# Main.net
KiCad netlist of a schematic drawn in Altium Designer
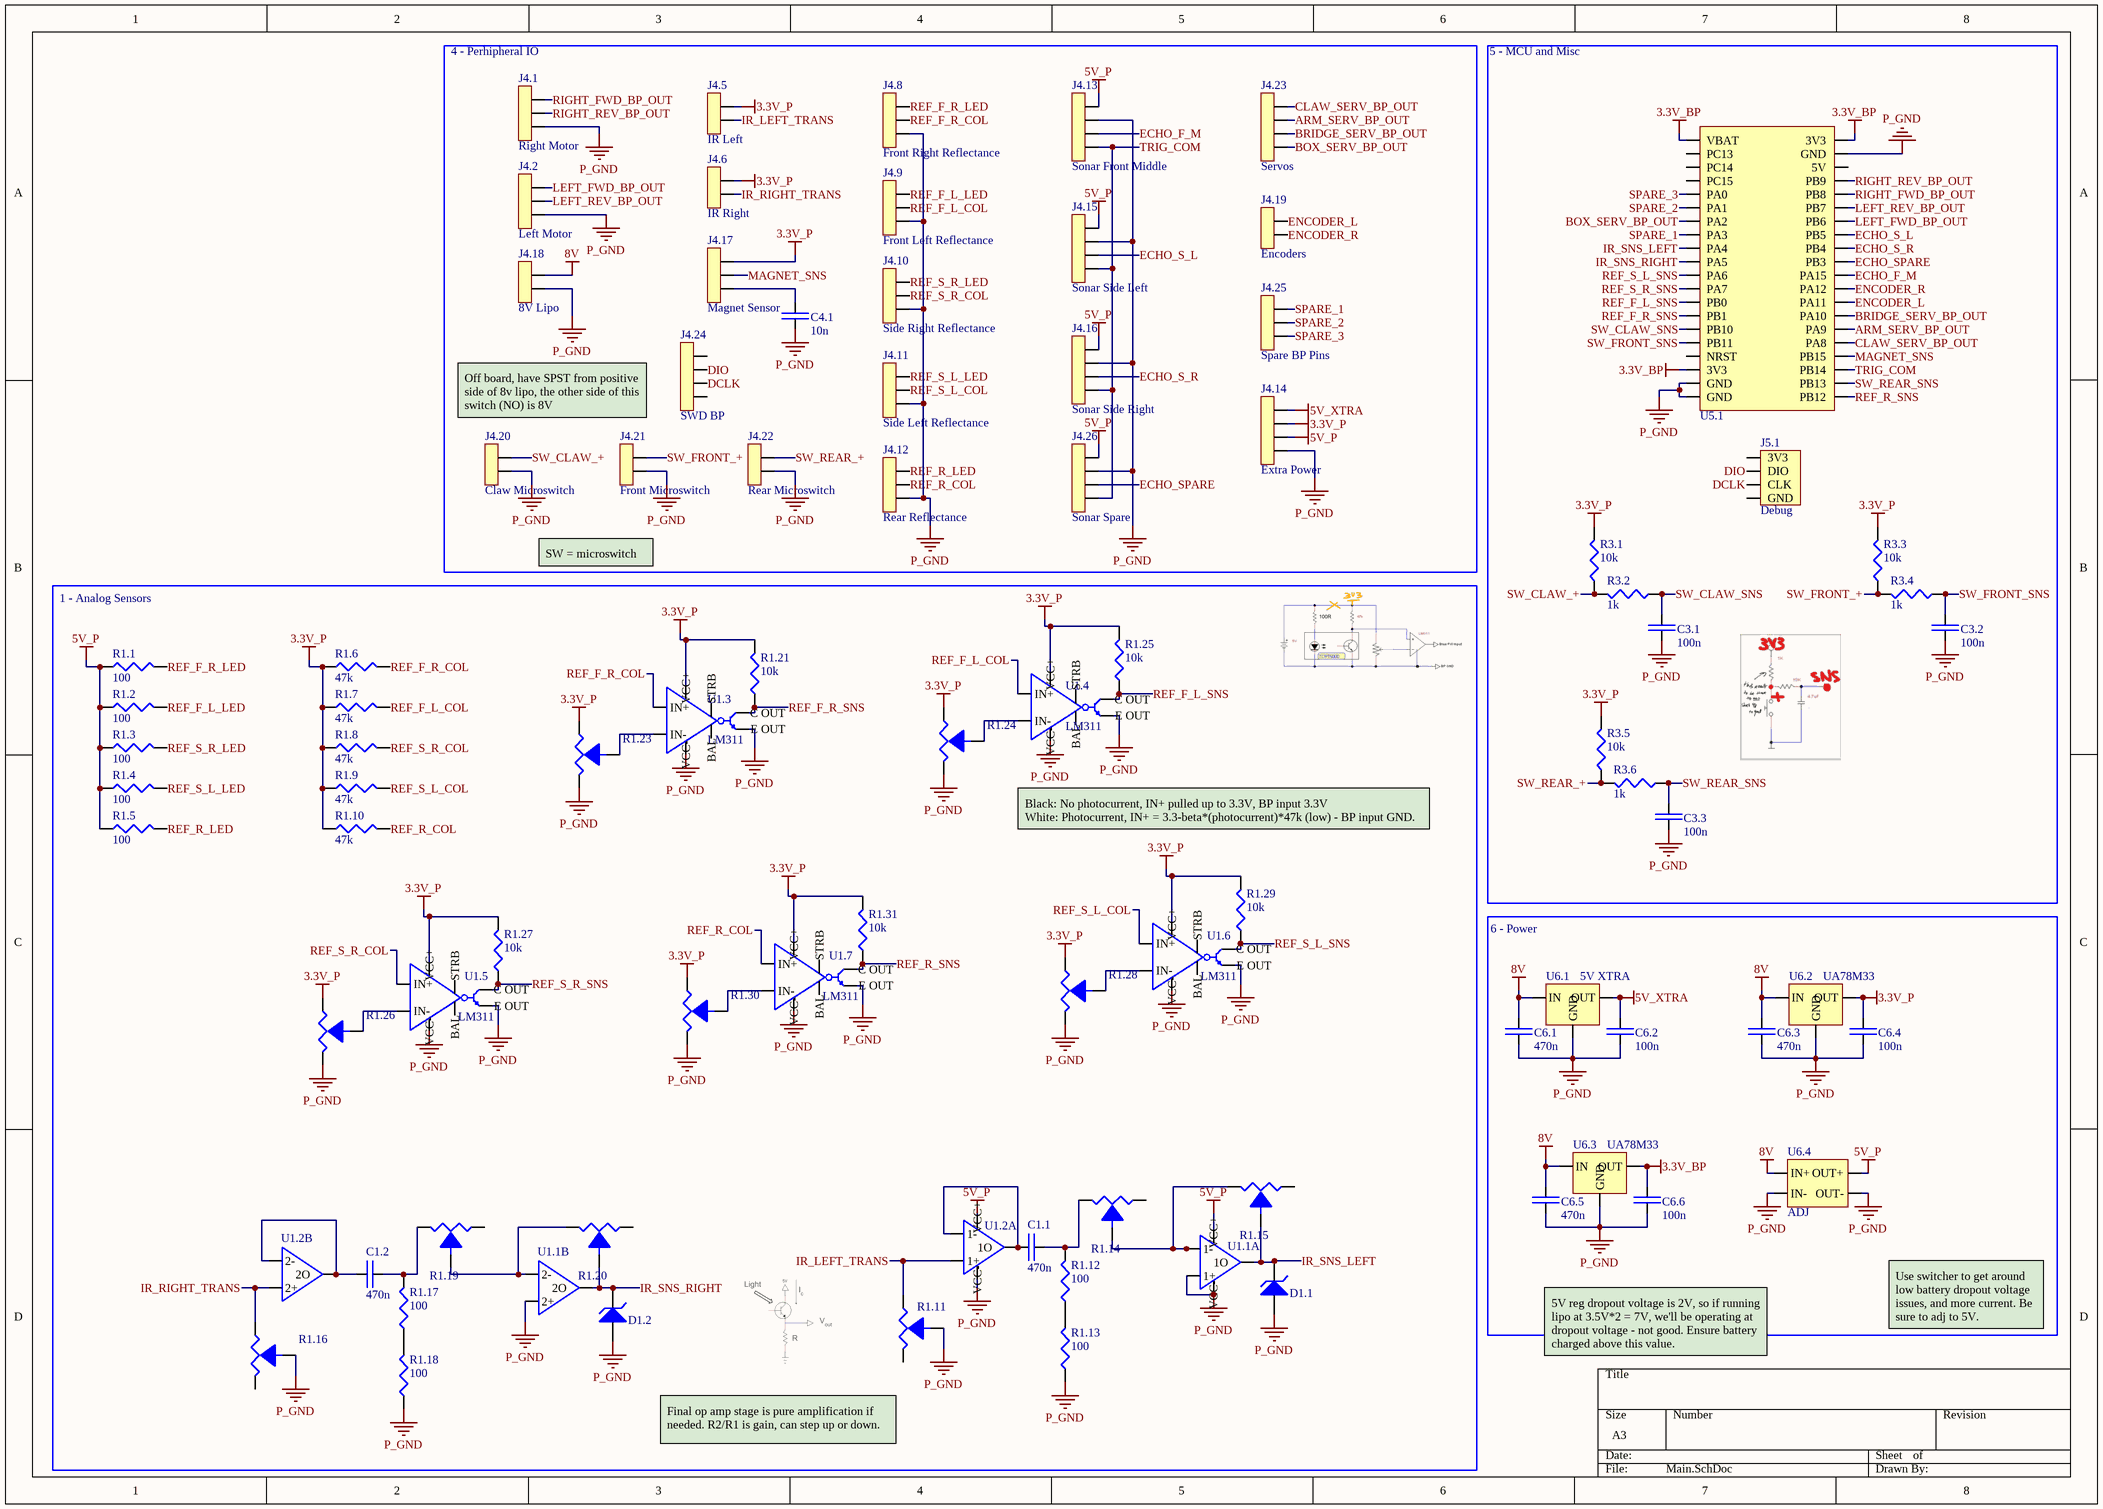
[diagram p0: Main.SchDoc]

(export (version "E")
  (design (tool "Eeschema 10.0.6"))
  (components
    (comp (ref "C1.1")
      (value "470n")
      (footprint "Non Polarized Cap")
      (libsource (lib "SPICEBot_SchLib") (part "Cap_Generic"))
    )
    (comp (ref "C1.2")
      (value "470n")
      (footprint "Non Polarized Cap")
      (libsource (lib "SPICEBot_SchLib") (part "Cap_Generic"))
    )
    (comp (ref "C3.1")
      (value "100n")
      (footprint "Non Polarized Cap")
      (libsource (lib "SPICEBot_SchLib") (part "Cap_Generic"))
    )
    (comp (ref "C3.2")
      (value "100n")
      (footprint "Non Polarized Cap")
      (libsource (lib "SPICEBot_SchLib") (part "Cap_Generic"))
    )
    (comp (ref "C3.3")
      (value "100n")
      (footprint "Non Polarized Cap")
      (libsource (lib "SPICEBot_SchLib") (part "Cap_Generic"))
    )
    (comp (ref "C4.1")
      (value "10n")
      (footprint "Non Polarized Cap")
      (libsource (lib "SPICEBot_SchLib") (part "Cap_Generic"))
    )
    (comp (ref "C6.1")
      (value "470n")
      (footprint "Non Polarized Cap")
      (libsource (lib "SPICEBot_SchLib") (part "Cap_Generic"))
    )
    (comp (ref "C6.2")
      (value "100n")
      (footprint "Non Polarized Cap")
      (libsource (lib "SPICEBot_SchLib") (part "Cap_Generic"))
    )
    (comp (ref "C6.3")
      (value "470n")
      (footprint "Non Polarized Cap")
      (libsource (lib "SPICEBot_SchLib") (part "Cap_Generic"))
    )
    (comp (ref "C6.4")
      (value "100n")
      (footprint "Non Polarized Cap")
      (libsource (lib "SPICEBot_SchLib") (part "Cap_Generic"))
    )
    (comp (ref "C6.5")
      (value "470n")
      (footprint "Non Polarized Cap")
      (libsource (lib "SPICEBot_SchLib") (part "Cap_Generic"))
    )
    (comp (ref "C6.6")
      (value "100n")
      (footprint "Non Polarized Cap")
      (libsource (lib "SPICEBot_SchLib") (part "Cap_Generic"))
    )
    (comp (ref "D1.1")
      (value "3.3V")
      (footprint "Zener Generic")
      (libsource (lib "SPICEBot_SchLib") (part "Zener_Generic"))
    )
    (comp (ref "D1.2")
      (value "3.3V")
      (footprint "Zener Generic")
      (libsource (lib "SPICEBot_SchLib") (part "Zener_Generic"))
    )
    (comp (ref "J4.1")
      (value "Right Motor")
      (footprint "3pos JST")
      (description "3pos Conn")
      (libsource (lib "SPICEBot_SchLib") (part "3pos Conn"))
    )
    (comp (ref "J4.2")
      (value "Left Motor")
      (footprint "3pos JST")
      (description "3pos Conn")
      (libsource (lib "SPICEBot_SchLib") (part "3pos Conn"))
    )
    (comp (ref "J4.5")
      (value "IR Left")
      (footprint "2pos JST")
      (description "2pos Conn JST")
      (libsource (lib "SPICEBot_SchLib") (part "2pos Conn"))
    )
    (comp (ref "J4.6")
      (value "IR Right")
      (footprint "2pos JST")
      (description "2pos Conn JST")
      (libsource (lib "SPICEBot_SchLib") (part "2pos Conn"))
    )
    (comp (ref "J4.8")
      (value "Front Right Reflectance")
      (footprint "3pos JST")
      (description "3pos Conn")
      (libsource (lib "SPICEBot_SchLib") (part "3pos Conn"))
    )
    (comp (ref "J4.9")
      (value "Front Left Reflectance")
      (footprint "3pos JST")
      (description "3pos Conn")
      (libsource (lib "SPICEBot_SchLib") (part "3pos Conn"))
    )
    (comp (ref "J4.10")
      (value "Side Right Reflectance")
      (footprint "3pos JST")
      (description "3pos Conn")
      (libsource (lib "SPICEBot_SchLib") (part "3pos Conn"))
    )
    (comp (ref "J4.11")
      (value "Side Left Reflectance")
      (footprint "3pos JST")
      (description "3pos Conn")
      (libsource (lib "SPICEBot_SchLib") (part "3pos Conn"))
    )
    (comp (ref "J4.12")
      (value "Rear Reflectance")
      (footprint "3pos JST")
      (description "3pos Conn")
      (libsource (lib "SPICEBot_SchLib") (part "3pos Conn"))
    )
    (comp (ref "J4.13")
      (value "Sonar Front Middle")
      (footprint "4Pos JST")
      (description "4pos Conn")
      (libsource (lib "SPICEBot_SchLib") (part "4pos Conn"))
    )
    (comp (ref "J4.14")
      (value "Extra Power")
      (footprint "4Pos JST")
      (description "4pos Conn")
      (libsource (lib "SPICEBot_SchLib") (part "4pos Conn"))
    )
    (comp (ref "J4.15")
      (value "Sonar Side Left")
      (footprint "4Pos JST")
      (description "4pos Conn")
      (libsource (lib "SPICEBot_SchLib") (part "4pos Conn"))
    )
    (comp (ref "J4.16")
      (value "Sonar Side Right")
      (footprint "4Pos JST")
      (description "4pos Conn")
      (libsource (lib "SPICEBot_SchLib") (part "4pos Conn"))
    )
    (comp (ref "J4.17")
      (value "Magnet Sensor")
      (footprint "3pos JST")
      (description "3pos Conn")
      (libsource (lib "SPICEBot_SchLib") (part "3pos Conn"))
    )
    (comp (ref "J4.18")
      (value "8V Lipo")
      (footprint "2pos JST")
      (description "2pos Conn JST")
      (libsource (lib "SPICEBot_SchLib") (part "2pos Conn"))
    )
    (comp (ref "J4.19")
      (value "Encoders")
      (footprint "2pos JST")
      (description "2pos Conn JST")
      (libsource (lib "SPICEBot_SchLib") (part "2pos Conn"))
    )
    (comp (ref "J4.20")
      (value "Claw Microswitch")
      (footprint "2pos JST")
      (description "2pos Conn JST")
      (libsource (lib "SPICEBot_SchLib") (part "2pos Conn"))
    )
    (comp (ref "J4.21")
      (value "Front Microswitch")
      (footprint "2pos JST")
      (description "2pos Conn JST")
      (libsource (lib "SPICEBot_SchLib") (part "2pos Conn"))
    )
    (comp (ref "J4.22")
      (value "Rear Microswitch")
      (footprint "2pos JST")
      (description "2pos Conn JST")
      (libsource (lib "SPICEBot_SchLib") (part "2pos Conn"))
    )
    (comp (ref "J4.23")
      (value "Servos")
      (footprint "4Pos JST")
      (description "4pos Conn")
      (libsource (lib "SPICEBot_SchLib") (part "4pos Conn"))
    )
    (comp (ref "J4.24")
      (value "SWD BP")
      (footprint "4Pos JST")
      (description "4pos Conn")
      (libsource (lib "SPICEBot_SchLib") (part "4pos Conn"))
    )
    (comp (ref "J4.25")
      (value "Spare BP Pins")
      (footprint "3pos JST")
      (description "3pos Conn")
      (libsource (lib "SPICEBot_SchLib") (part "3pos Conn"))
    )
    (comp (ref "J4.26")
      (value "Sonar Spare")
      (footprint "4Pos JST")
      (description "4pos Conn")
      (libsource (lib "SPICEBot_SchLib") (part "4pos Conn"))
    )
    (comp (ref "J5.1")
      (value "Debug")
      (footprint "Four Pads")
      (libsource (lib "SPICEBot_SchLib") (part "BP SWD Conn"))
    )
    (comp (ref "R1.1")
      (value "100")
      (footprint "Res_Generic")
      (libsource (lib "SPICEBot_SchLib") (part "Res_Generic"))
    )
    (comp (ref "R1.2")
      (value "100")
      (footprint "Res_Generic")
      (libsource (lib "SPICEBot_SchLib") (part "Res_Generic"))
    )
    (comp (ref "R1.3")
      (value "100")
      (footprint "Res_Generic")
      (libsource (lib "SPICEBot_SchLib") (part "Res_Generic"))
    )
    (comp (ref "R1.4")
      (value "100")
      (footprint "Res_Generic")
      (libsource (lib "SPICEBot_SchLib") (part "Res_Generic"))
    )
    (comp (ref "R1.5")
      (value "100")
      (footprint "Res_Generic")
      (libsource (lib "SPICEBot_SchLib") (part "Res_Generic"))
    )
    (comp (ref "R1.6")
      (value "47k")
      (footprint "Res_Generic")
      (libsource (lib "SPICEBot_SchLib") (part "Res_Generic"))
    )
    (comp (ref "R1.7")
      (value "47k")
      (footprint "Res_Generic")
      (libsource (lib "SPICEBot_SchLib") (part "Res_Generic"))
    )
    (comp (ref "R1.8")
      (value "47k")
      (footprint "Res_Generic")
      (libsource (lib "SPICEBot_SchLib") (part "Res_Generic"))
    )
    (comp (ref "R1.9")
      (value "47k")
      (footprint "Res_Generic")
      (libsource (lib "SPICEBot_SchLib") (part "Res_Generic"))
    )
    (comp (ref "R1.10")
      (value "47k")
      (footprint "Res_Generic")
      (libsource (lib "SPICEBot_SchLib") (part "Res_Generic"))
    )
    (comp (ref "R1.11")
      (value "100k")
      (footprint "Pot Generic")
      (libsource (lib "SPICEBot_SchLib") (part "Pot_Generic"))
    )
    (comp (ref "R1.12")
      (value "100")
      (footprint "Res_Generic")
      (libsource (lib "SPICEBot_SchLib") (part "Res_Generic"))
    )
    (comp (ref "R1.13")
      (value "100")
      (footprint "Res_Generic")
      (libsource (lib "SPICEBot_SchLib") (part "Res_Generic"))
    )
    (comp (ref "R1.14")
      (value "10k")
      (footprint "Pot Generic")
      (libsource (lib "SPICEBot_SchLib") (part "Pot_Generic"))
    )
    (comp (ref "R1.15")
      (value "100k")
      (footprint "Pot Generic")
      (libsource (lib "SPICEBot_SchLib") (part "Pot_Generic"))
    )
    (comp (ref "R1.16")
      (value "100k")
      (footprint "Pot Generic")
      (libsource (lib "SPICEBot_SchLib") (part "Pot_Generic"))
    )
    (comp (ref "R1.17")
      (value "100")
      (footprint "Res_Generic")
      (libsource (lib "SPICEBot_SchLib") (part "Res_Generic"))
    )
    (comp (ref "R1.18")
      (value "100")
      (footprint "Res_Generic")
      (libsource (lib "SPICEBot_SchLib") (part "Res_Generic"))
    )
    (comp (ref "R1.19")
      (value "10k")
      (footprint "Pot Generic")
      (libsource (lib "SPICEBot_SchLib") (part "Pot_Generic"))
    )
    (comp (ref "R1.20")
      (value "100k")
      (footprint "Pot Generic")
      (libsource (lib "SPICEBot_SchLib") (part "Pot_Generic"))
    )
    (comp (ref "R1.21")
      (value "10k")
      (footprint "Res_Generic")
      (libsource (lib "SPICEBot_SchLib") (part "Res_Generic"))
    )
    (comp (ref "R1.23")
      (value "10k")
      (footprint "Pot Generic")
      (libsource (lib "SPICEBot_SchLib") (part "Pot_Generic"))
    )
    (comp (ref "R1.24")
      (value "10k")
      (footprint "Pot Generic")
      (libsource (lib "SPICEBot_SchLib") (part "Pot_Generic"))
    )
    (comp (ref "R1.25")
      (value "10k")
      (footprint "Res_Generic")
      (libsource (lib "SPICEBot_SchLib") (part "Res_Generic"))
    )
    (comp (ref "R1.26")
      (value "10k")
      (footprint "Pot Generic")
      (libsource (lib "SPICEBot_SchLib") (part "Pot_Generic"))
    )
    (comp (ref "R1.27")
      (value "10k")
      (footprint "Res_Generic")
      (libsource (lib "SPICEBot_SchLib") (part "Res_Generic"))
    )
    (comp (ref "R1.28")
      (value "10k")
      (footprint "Pot Generic")
      (libsource (lib "SPICEBot_SchLib") (part "Pot_Generic"))
    )
    (comp (ref "R1.29")
      (value "10k")
      (footprint "Res_Generic")
      (libsource (lib "SPICEBot_SchLib") (part "Res_Generic"))
    )
    (comp (ref "R1.30")
      (value "10k")
      (footprint "Pot Generic")
      (libsource (lib "SPICEBot_SchLib") (part "Pot_Generic"))
    )
    (comp (ref "R1.31")
      (value "10k")
      (footprint "Res_Generic")
      (libsource (lib "SPICEBot_SchLib") (part "Res_Generic"))
    )
    (comp (ref "R3.1")
      (value "10k")
      (footprint "Res_Generic")
      (libsource (lib "SPICEBot_SchLib") (part "Res_Generic"))
    )
    (comp (ref "R3.2")
      (value "1k")
      (footprint "Res_Generic")
      (libsource (lib "SPICEBot_SchLib") (part "Res_Generic"))
    )
    (comp (ref "R3.3")
      (value "10k")
      (footprint "Res_Generic")
      (libsource (lib "SPICEBot_SchLib") (part "Res_Generic"))
    )
    (comp (ref "R3.4")
      (value "1k")
      (footprint "Res_Generic")
      (libsource (lib "SPICEBot_SchLib") (part "Res_Generic"))
    )
    (comp (ref "R3.5")
      (value "10k")
      (footprint "Res_Generic")
      (libsource (lib "SPICEBot_SchLib") (part "Res_Generic"))
    )
    (comp (ref "R3.6")
      (value "1k")
      (footprint "Res_Generic")
      (libsource (lib "SPICEBot_SchLib") (part "Res_Generic"))
    )
    (comp (ref "U1.1")
      (value "TL082IP")
      (footprint "DIP8")
      (description "TL082IP IC OPAMP JFET 2 CIRCUIT 8DIP")
      (libsource (lib "SPICEBot_SchLib") (part "TL082IP Op Amp"))
    )
    (comp (ref "U1.2")
      (value "TL082IP")
      (footprint "DIP8")
      (description "TL082IP IC OPAMP JFET 2 CIRCUIT 8DIP")
      (libsource (lib "SPICEBot_SchLib") (part "TL082IP Op Amp"))
    )
    (comp (ref "U1.3")
      (value "LM311")
      (footprint "DIP8")
      (description "LM311 IC DIFF COMPARATOR STROBE 8-DIP")
      (libsource (lib "SPICEBot_SchLib") (part "LM311 Comparator"))
    )
    (comp (ref "U1.4")
      (value "LM311")
      (footprint "DIP8")
      (description "LM311 IC DIFF COMPARATOR STROBE 8-DIP")
      (libsource (lib "SPICEBot_SchLib") (part "LM311 Comparator"))
    )
    (comp (ref "U1.5")
      (value "LM311")
      (footprint "DIP8")
      (description "LM311 IC DIFF COMPARATOR STROBE 8-DIP")
      (libsource (lib "SPICEBot_SchLib") (part "LM311 Comparator"))
    )
    (comp (ref "U1.6")
      (value "LM311")
      (footprint "DIP8")
      (description "LM311 IC DIFF COMPARATOR STROBE 8-DIP")
      (libsource (lib "SPICEBot_SchLib") (part "LM311 Comparator"))
    )
    (comp (ref "U1.7")
      (value "LM311")
      (footprint "DIP8")
      (description "LM311 IC DIFF COMPARATOR STROBE 8-DIP")
      (libsource (lib "SPICEBot_SchLib") (part "LM311 Comparator"))
    )
    (comp (ref "U5.1")
      (value "Bluepill")
      (footprint "DIP40")
      (description "STM32F103C8T6")
      (libsource (lib "SPICEBot_SchLib") (part "Bluepill"))
    )
    (comp (ref "U6.1")
      (value "5V XTRA")
      (footprint "TO220")
      (description "UA7805 IC REG LINEAR 5V 1.5A TO220-3")
      (libsource (lib "SPICEBot_SchLib") (part "UA7805 5V Reg"))
    )
    (comp (ref "U6.2")
      (value "UA78M33")
      (footprint "TO220")
      (description "UA78M33 IC REG LINEAR 3.3V 500MA TO220-3")
      (libsource (lib "SPICEBot_SchLib") (part "UA78M33CKCS 3.3V Reg"))
    )
    (comp (ref "U6.3")
      (value "UA78M33")
      (footprint "TO220")
      (description "UA78M33 IC REG LINEAR 3.3V 500MA TO220-3")
      (libsource (lib "SPICEBot_SchLib") (part "UA78M33CKCS 3.3V Reg"))
    )
    (comp (ref "U6.4")
      (value "ADJ")
      (footprint "ADJ Switcher")
      (description "Adjutable Switcher 3.5A Max")
      (libsource (lib "SPICEBot_SchLib") (part "LM2596S"))
    )
  )
  (nets
    (net (code "1") (name "/ARM_SERV_BP_OUT") (class "Default")
      (node (ref "J4.23") (pin "3") (pinfunction "3_3") (pintype "passive"))
      (node (ref "U5.1") (pin "26") (pinfunction "PA9_26") (pintype "passive"))
    )
    (net (code "2") (name "/BOX_SERV_BP_OUT") (class "Default")
      (node (ref "J4.23") (pin "1") (pinfunction "1_1") (pintype "passive"))
      (node (ref "U5.1") (pin "7") (pinfunction "PA2_7") (pintype "passive"))
    )
    (net (code "3") (name "/BRIDGE_SERV_BP_OUT") (class "Default")
      (node (ref "J4.23") (pin "2") (pinfunction "2_2") (pintype "passive"))
      (node (ref "U5.1") (pin "27") (pinfunction "PA10_27") (pintype "passive"))
    )
    (net (code "4") (name "/CLAW_SERV_BP_OUT") (class "Default")
      (node (ref "J4.23") (pin "4") (pinfunction "4_4") (pintype "passive"))
      (node (ref "U5.1") (pin "25") (pinfunction "PA8_25") (pintype "passive"))
    )
    (net (code "5") (name "/DCLK") (class "Default")
      (node (ref "J4.24") (pin "2") (pinfunction "2_2") (pintype "passive"))
      (node (ref "J5.1") (pin "3") (pinfunction "CLK_3") (pintype "passive"))
    )
    (net (code "6") (name "/DIO") (class "Default")
      (node (ref "J4.24") (pin "3") (pinfunction "3_3") (pintype "passive"))
      (node (ref "J5.1") (pin "2") (pinfunction "DIO_2") (pintype "passive"))
    )
    (net (code "7") (name "/ECHO_F_M") (class "Default")
      (node (ref "J4.13") (pin "2") (pinfunction "2_2") (pintype "passive"))
      (node (ref "U5.1") (pin "30") (pinfunction "PA15_30") (pintype "passive"))
    )
    (net (code "8") (name "/ECHO_SPARE") (class "Default")
      (node (ref "J4.26") (pin "2") (pinfunction "2_2") (pintype "passive"))
      (node (ref "U5.1") (pin "31") (pinfunction "PB3_31") (pintype "passive"))
    )
    (net (code "9") (name "/ECHO_S_L") (class "Default")
      (node (ref "J4.15") (pin "2") (pinfunction "2_2") (pintype "passive"))
      (node (ref "U5.1") (pin "33") (pinfunction "PB5_33") (pintype "passive"))
    )
    (net (code "10") (name "/ECHO_S_R") (class "Default")
      (node (ref "J4.16") (pin "2") (pinfunction "2_2") (pintype "passive"))
      (node (ref "U5.1") (pin "32") (pinfunction "PB4_32") (pintype "passive"))
    )
    (net (code "11") (name "/ENCODER_L") (class "Default")
      (node (ref "J4.19") (pin "2") (pinfunction "2_2") (pintype "passive"))
      (node (ref "U5.1") (pin "28") (pinfunction "PA11_28") (pintype "passive"))
    )
    (net (code "12") (name "/ENCODER_R") (class "Default")
      (node (ref "J4.19") (pin "1") (pinfunction "1_1") (pintype "passive"))
      (node (ref "U5.1") (pin "29") (pinfunction "PA12_29") (pintype "passive"))
    )
    (net (code "13") (name "/IR_LEFT_TRANS") (class "Default")
      (node (ref "J4.5") (pin "1") (pinfunction "1_1") (pintype "passive"))
      (node (ref "R1.11") (pin "3") (pinfunction "3_3") (pintype "passive"))
      (node (ref "U1.2") (pin "3") (pinfunction "1+_3") (pintype "passive"))
    )
    (net (code "14") (name "/IR_RIGHT_TRANS") (class "Default")
      (node (ref "J4.6") (pin "1") (pinfunction "1_1") (pintype "passive"))
      (node (ref "R1.16") (pin "3") (pinfunction "3_3") (pintype "passive"))
      (node (ref "U1.2") (pin "5") (pinfunction "2+_5") (pintype "passive"))
    )
    (net (code "15") (name "/IR_SNS_LEFT") (class "Default")
      (node (ref "D1.1") (pin "2") (pinfunction "Cathode_2") (pintype "passive"))
      (node (ref "R1.15") (pin "2") (pinfunction "2_2") (pintype "passive"))
      (node (ref "U1.1") (pin "1") (pinfunction "1O_1") (pintype "passive"))
      (node (ref "U5.1") (pin "9") (pinfunction "PA4_9") (pintype "passive"))
    )
    (net (code "16") (name "/IR_SNS_RIGHT") (class "Default")
      (node (ref "D1.2") (pin "2") (pinfunction "Cathode_2") (pintype "passive"))
      (node (ref "R1.20") (pin "2") (pinfunction "2_2") (pintype "passive"))
      (node (ref "U1.1") (pin "7") (pinfunction "2O_7") (pintype "passive"))
      (node (ref "U5.1") (pin "10") (pinfunction "PA5_10") (pintype "passive"))
    )
    (net (code "17") (name "/LEFT_FWD_BP_OUT") (class "Default")
      (node (ref "J4.2") (pin "3") (pinfunction "3_3") (pintype "passive"))
      (node (ref "U5.1") (pin "34") (pinfunction "PB6_34") (pintype "passive"))
    )
    (net (code "18") (name "/LEFT_REV_BP_OUT") (class "Default")
      (node (ref "J4.2") (pin "2") (pinfunction "2_2") (pintype "passive"))
      (node (ref "U5.1") (pin "35") (pinfunction "PB7_35") (pintype "passive"))
    )
    (net (code "19") (name "/MAGNET_SNS") (class "Default")
      (node (ref "J4.17") (pin "2") (pinfunction "2_2") (pintype "passive"))
      (node (ref "U5.1") (pin "24") (pinfunction "PB15_24") (pintype "passive"))
    )
    (net (code "20") (name "/REF_F_L_COL") (class "Default")
      (node (ref "J4.9") (pin "2") (pinfunction "2_2") (pintype "passive"))
      (node (ref "R1.7") (pin "2") (pinfunction "2_2") (pintype "passive"))
      (node (ref "U1.4") (pin "2") (pinfunction "IN+_2") (pintype "passive"))
    )
    (net (code "21") (name "/REF_F_L_LED") (class "Default")
      (node (ref "J4.9") (pin "3") (pinfunction "3_3") (pintype "passive"))
      (node (ref "R1.2") (pin "2") (pinfunction "2_2") (pintype "passive"))
    )
    (net (code "22") (name "/REF_F_L_SNS") (class "Default")
      (node (ref "R1.25") (pin "1") (pinfunction "1_1") (pintype "passive"))
      (node (ref "U1.4") (pin "7") (pinfunction "C_OUT_7") (pintype "passive"))
      (node (ref "U5.1") (pin "13") (pinfunction "PB0_13") (pintype "passive"))
    )
    (net (code "23") (name "/REF_F_R_COL") (class "Default")
      (node (ref "J4.8") (pin "2") (pinfunction "2_2") (pintype "passive"))
      (node (ref "R1.6") (pin "2") (pinfunction "2_2") (pintype "passive"))
      (node (ref "U1.3") (pin "2") (pinfunction "IN+_2") (pintype "passive"))
    )
    (net (code "24") (name "/REF_F_R_LED") (class "Default")
      (node (ref "J4.8") (pin "3") (pinfunction "3_3") (pintype "passive"))
      (node (ref "R1.1") (pin "2") (pinfunction "2_2") (pintype "passive"))
    )
    (net (code "25") (name "/REF_F_R_SNS") (class "Default")
      (node (ref "R1.21") (pin "1") (pinfunction "1_1") (pintype "passive"))
      (node (ref "U1.3") (pin "7") (pinfunction "C_OUT_7") (pintype "passive"))
      (node (ref "U5.1") (pin "14") (pinfunction "PB1_14") (pintype "passive"))
    )
    (net (code "26") (name "/REF_R_COL") (class "Default")
      (node (ref "J4.12") (pin "2") (pinfunction "2_2") (pintype "passive"))
      (node (ref "R1.10") (pin "2") (pinfunction "2_2") (pintype "passive"))
      (node (ref "U1.7") (pin "2") (pinfunction "IN+_2") (pintype "passive"))
    )
    (net (code "27") (name "/REF_R_LED") (class "Default")
      (node (ref "J4.12") (pin "3") (pinfunction "3_3") (pintype "passive"))
      (node (ref "R1.5") (pin "2") (pinfunction "2_2") (pintype "passive"))
    )
    (net (code "28") (name "/REF_R_SNS") (class "Default")
      (node (ref "R1.31") (pin "1") (pinfunction "1_1") (pintype "passive"))
      (node (ref "U1.7") (pin "7") (pinfunction "C_OUT_7") (pintype "passive"))
      (node (ref "U5.1") (pin "21") (pinfunction "PB12_21") (pintype "passive"))
    )
    (net (code "29") (name "/REF_S_L_COL") (class "Default")
      (node (ref "J4.11") (pin "2") (pinfunction "2_2") (pintype "passive"))
      (node (ref "R1.9") (pin "2") (pinfunction "2_2") (pintype "passive"))
      (node (ref "U1.6") (pin "2") (pinfunction "IN+_2") (pintype "passive"))
    )
    (net (code "30") (name "/REF_S_L_LED") (class "Default")
      (node (ref "J4.11") (pin "3") (pinfunction "3_3") (pintype "passive"))
      (node (ref "R1.4") (pin "2") (pinfunction "2_2") (pintype "passive"))
    )
    (net (code "31") (name "/REF_S_L_SNS") (class "Default")
      (node (ref "R1.29") (pin "1") (pinfunction "1_1") (pintype "passive"))
      (node (ref "U1.6") (pin "7") (pinfunction "C_OUT_7") (pintype "passive"))
      (node (ref "U5.1") (pin "11") (pinfunction "PA6_11") (pintype "passive"))
    )
    (net (code "32") (name "/REF_S_R_COL") (class "Default")
      (node (ref "J4.10") (pin "2") (pinfunction "2_2") (pintype "passive"))
      (node (ref "R1.8") (pin "2") (pinfunction "2_2") (pintype "passive"))
      (node (ref "U1.5") (pin "2") (pinfunction "IN+_2") (pintype "passive"))
    )
    (net (code "33") (name "/REF_S_R_LED") (class "Default")
      (node (ref "J4.10") (pin "3") (pinfunction "3_3") (pintype "passive"))
      (node (ref "R1.3") (pin "2") (pinfunction "2_2") (pintype "passive"))
    )
    (net (code "34") (name "/REF_S_R_SNS") (class "Default")
      (node (ref "R1.27") (pin "1") (pinfunction "1_1") (pintype "passive"))
      (node (ref "U1.5") (pin "7") (pinfunction "C_OUT_7") (pintype "passive"))
      (node (ref "U5.1") (pin "12") (pinfunction "PA7_12") (pintype "passive"))
    )
    (net (code "35") (name "/RIGHT_FWD_BP_OUT") (class "Default")
      (node (ref "J4.1") (pin "3") (pinfunction "3_3") (pintype "passive"))
      (node (ref "U5.1") (pin "36") (pinfunction "PB8_36") (pintype "passive"))
    )
    (net (code "36") (name "/RIGHT_REV_BP_OUT") (class "Default")
      (node (ref "J4.1") (pin "2") (pinfunction "2_2") (pintype "passive"))
      (node (ref "U5.1") (pin "37") (pinfunction "PB9_37") (pintype "passive"))
    )
    (net (code "37") (name "/SPARE_1") (class "Default")
      (node (ref "J4.25") (pin "3") (pinfunction "3_3") (pintype "passive"))
      (node (ref "U5.1") (pin "8") (pinfunction "PA3_8") (pintype "passive"))
    )
    (net (code "38") (name "/SPARE_2") (class "Default")
      (node (ref "J4.25") (pin "2") (pinfunction "2_2") (pintype "passive"))
      (node (ref "U5.1") (pin "6") (pinfunction "PA1_6") (pintype "passive"))
    )
    (net (code "39") (name "/SPARE_3") (class "Default")
      (node (ref "J4.25") (pin "1") (pinfunction "1_1") (pintype "passive"))
      (node (ref "U5.1") (pin "5") (pinfunction "PA0_5") (pintype "passive"))
    )
    (net (code "40") (name "/SW_CLAW_+") (class "Default")
      (node (ref "J4.20") (pin "2") (pinfunction "2_2") (pintype "passive"))
      (node (ref "R3.1") (pin "1") (pinfunction "1_1") (pintype "passive"))
      (node (ref "R3.2") (pin "2") (pinfunction "2_2") (pintype "passive"))
    )
    (net (code "41") (name "/SW_CLAW_SNS") (class "Default")
      (node (ref "C3.1") (pin "2") (pinfunction "2_2") (pintype "passive"))
      (node (ref "R3.2") (pin "1") (pinfunction "1_1") (pintype "passive"))
      (node (ref "U5.1") (pin "15") (pinfunction "PB10_15") (pintype "passive"))
    )
    (net (code "42") (name "/SW_FRONT_+") (class "Default")
      (node (ref "J4.21") (pin "2") (pinfunction "2_2") (pintype "passive"))
      (node (ref "R3.3") (pin "1") (pinfunction "1_1") (pintype "passive"))
      (node (ref "R3.4") (pin "2") (pinfunction "2_2") (pintype "passive"))
    )
    (net (code "43") (name "/SW_FRONT_SNS") (class "Default")
      (node (ref "C3.2") (pin "2") (pinfunction "2_2") (pintype "passive"))
      (node (ref "R3.4") (pin "1") (pinfunction "1_1") (pintype "passive"))
      (node (ref "U5.1") (pin "16") (pinfunction "PB11_16") (pintype "passive"))
    )
    (net (code "44") (name "/SW_REAR_+") (class "Default")
      (node (ref "J4.22") (pin "2") (pinfunction "2_2") (pintype "passive"))
      (node (ref "R3.5") (pin "1") (pinfunction "1_1") (pintype "passive"))
      (node (ref "R3.6") (pin "2") (pinfunction "2_2") (pintype "passive"))
    )
    (net (code "45") (name "/SW_REAR_SNS") (class "Default")
      (node (ref "C3.3") (pin "2") (pinfunction "2_2") (pintype "passive"))
      (node (ref "R3.6") (pin "1") (pinfunction "1_1") (pintype "passive"))
      (node (ref "U5.1") (pin "22") (pinfunction "PB13_22") (pintype "passive"))
    )
    (net (code "46") (name "/TRIG_COM") (class "Default")
      (node (ref "J4.13") (pin "1") (pinfunction "1_1") (pintype "passive"))
      (node (ref "J4.15") (pin "1") (pinfunction "1_1") (pintype "passive"))
      (node (ref "J4.16") (pin "1") (pinfunction "1_1") (pintype "passive"))
      (node (ref "J4.26") (pin "1") (pinfunction "1_1") (pintype "passive"))
      (node (ref "U5.1") (pin "23") (pinfunction "PB14_23") (pintype "passive"))
    )
    (net (code "47") (name "3.3V_BP") (class "Default")
      (node (ref "C6.6") (pin "2") (pinfunction "2_2") (pintype "passive"))
      (node (ref "U5.1") (pin "1") (pinfunction "VBAT_1") (pintype "passive"))
      (node (ref "U5.1") (pin "18") (pinfunction "3V3_18") (pintype "passive"))
      (node (ref "U5.1") (pin "40") (pinfunction "3V3_40") (pintype "passive"))
      (node (ref "U6.3") (pin "3") (pinfunction "OUT_3") (pintype "passive"))
    )
    (net (code "48") (name "3.3V_P") (class "Default")
      (node (ref "C6.4") (pin "2") (pinfunction "2_2") (pintype "passive"))
      (node (ref "J4.14") (pin "3") (pinfunction "3_3") (pintype "passive"))
      (node (ref "J4.17") (pin "3") (pinfunction "3_3") (pintype "passive"))
      (node (ref "J4.5") (pin "2") (pinfunction "2_2") (pintype "passive"))
      (node (ref "J4.6") (pin "2") (pinfunction "2_2") (pintype "passive"))
      (node (ref "R1.10") (pin "1") (pinfunction "1_1") (pintype "passive"))
      (node (ref "R1.21") (pin "2") (pinfunction "2_2") (pintype "passive"))
      (node (ref "R1.23") (pin "3") (pinfunction "3_3") (pintype "passive"))
      (node (ref "R1.24") (pin "3") (pinfunction "3_3") (pintype "passive"))
      (node (ref "R1.25") (pin "2") (pinfunction "2_2") (pintype "passive"))
      (node (ref "R1.26") (pin "3") (pinfunction "3_3") (pintype "passive"))
      (node (ref "R1.27") (pin "2") (pinfunction "2_2") (pintype "passive"))
      (node (ref "R1.28") (pin "3") (pinfunction "3_3") (pintype "passive"))
      (node (ref "R1.29") (pin "2") (pinfunction "2_2") (pintype "passive"))
      (node (ref "R1.30") (pin "3") (pinfunction "3_3") (pintype "passive"))
      (node (ref "R1.31") (pin "2") (pinfunction "2_2") (pintype "passive"))
      (node (ref "R1.6") (pin "1") (pinfunction "1_1") (pintype "passive"))
      (node (ref "R1.7") (pin "1") (pinfunction "1_1") (pintype "passive"))
      (node (ref "R1.8") (pin "1") (pinfunction "1_1") (pintype "passive"))
      (node (ref "R1.9") (pin "1") (pinfunction "1_1") (pintype "passive"))
      (node (ref "R3.1") (pin "2") (pinfunction "2_2") (pintype "passive"))
      (node (ref "R3.3") (pin "2") (pinfunction "2_2") (pintype "passive"))
      (node (ref "R3.5") (pin "2") (pinfunction "2_2") (pintype "passive"))
      (node (ref "U1.3") (pin "8") (pinfunction "VCC+_8") (pintype "passive"))
      (node (ref "U1.4") (pin "8") (pinfunction "VCC+_8") (pintype "passive"))
      (node (ref "U1.5") (pin "8") (pinfunction "VCC+_8") (pintype "passive"))
      (node (ref "U1.6") (pin "8") (pinfunction "VCC+_8") (pintype "passive"))
      (node (ref "U1.7") (pin "8") (pinfunction "VCC+_8") (pintype "passive"))
      (node (ref "U6.2") (pin "3") (pinfunction "OUT_3") (pintype "passive"))
    )
    (net (code "49") (name "5V_P") (class "Default")
      (node (ref "J4.13") (pin "4") (pinfunction "4_4") (pintype "passive"))
      (node (ref "J4.14") (pin "2") (pinfunction "2_2") (pintype "passive"))
      (node (ref "J4.15") (pin "4") (pinfunction "4_4") (pintype "passive"))
      (node (ref "J4.16") (pin "4") (pinfunction "4_4") (pintype "passive"))
      (node (ref "J4.26") (pin "4") (pinfunction "4_4") (pintype "passive"))
      (node (ref "R1.1") (pin "1") (pinfunction "1_1") (pintype "passive"))
      (node (ref "R1.2") (pin "1") (pinfunction "1_1") (pintype "passive"))
      (node (ref "R1.3") (pin "1") (pinfunction "1_1") (pintype "passive"))
      (node (ref "R1.4") (pin "1") (pinfunction "1_1") (pintype "passive"))
      (node (ref "R1.5") (pin "1") (pinfunction "1_1") (pintype "passive"))
      (node (ref "U1.1") (pin "8") (pinfunction "VCC+_8") (pintype "passive"))
      (node (ref "U1.2") (pin "8") (pinfunction "VCC+_8") (pintype "passive"))
      (node (ref "U6.4") (pin "4") (pinfunction "OUT+_4") (pintype "passive"))
    )
    (net (code "50") (name "5V_XTRA") (class "Default")
      (node (ref "C6.2") (pin "2") (pinfunction "2_2") (pintype "passive"))
      (node (ref "J4.14") (pin "4") (pinfunction "4_4") (pintype "passive"))
      (node (ref "U6.1") (pin "3") (pinfunction "OUT_3") (pintype "passive"))
    )
    (net (code "51") (name "8V") (class "Default")
      (node (ref "C6.1") (pin "2") (pinfunction "2_2") (pintype "passive"))
      (node (ref "C6.3") (pin "2") (pinfunction "2_2") (pintype "passive"))
      (node (ref "C6.5") (pin "2") (pinfunction "2_2") (pintype "passive"))
      (node (ref "J4.18") (pin "2") (pinfunction "2_2") (pintype "passive"))
      (node (ref "U6.1") (pin "1") (pinfunction "IN_1") (pintype "passive"))
      (node (ref "U6.2") (pin "1") (pinfunction "IN_1") (pintype "passive"))
      (node (ref "U6.3") (pin "1") (pinfunction "IN_1") (pintype "passive"))
      (node (ref "U6.4") (pin "1") (pinfunction "IN+_1") (pintype "passive"))
    )
    (net (code "52") (name "Net-(C1.1-Pad2)") (class "Default")
      (node (ref "C1.1") (pin "2") (pinfunction "2_2") (pintype "passive"))
      (node (ref "R1.12") (pin "2") (pinfunction "2_2") (pintype "passive"))
      (node (ref "R1.14") (pin "1") (pinfunction "1_1") (pintype "passive"))
    )
    (net (code "53") (name "Net-(C1.2-Pad2)") (class "Default")
      (node (ref "C1.2") (pin "2") (pinfunction "2_2") (pintype "passive"))
      (node (ref "R1.17") (pin "2") (pinfunction "2_2") (pintype "passive"))
      (node (ref "R1.19") (pin "1") (pinfunction "1_1") (pintype "passive"))
    )
    (net (code "54") (name "Net-(C4.1-Pad2)") (class "Default")
      (node (ref "C4.1") (pin "2") (pinfunction "2_2") (pintype "passive"))
      (node (ref "J4.17") (pin "1") (pinfunction "1_1") (pintype "passive"))
    )
    (net (code "55") (name "Net-(R1.12-Pad1)") (class "Default")
      (node (ref "R1.12") (pin "1") (pinfunction "1_1") (pintype "passive"))
      (node (ref "R1.13") (pin "2") (pinfunction "2_2") (pintype "passive"))
    )
    (net (code "56") (name "Net-(R1.17-Pad1)") (class "Default")
      (node (ref "R1.17") (pin "1") (pinfunction "1_1") (pintype "passive"))
      (node (ref "R1.18") (pin "2") (pinfunction "2_2") (pintype "passive"))
    )
    (net (code "57") (name "Net-(U1.1A-1-)") (class "Default")
      (node (ref "R1.14") (pin "2") (pinfunction "2_2") (pintype "passive"))
      (node (ref "R1.15") (pin "1") (pinfunction "1_1") (pintype "passive"))
      (node (ref "U1.1") (pin "2") (pinfunction "1-_2") (pintype "passive"))
    )
    (net (code "58") (name "Net-(U1.1B-2-)") (class "Default")
      (node (ref "R1.19") (pin "2") (pinfunction "2_2") (pintype "passive"))
      (node (ref "R1.20") (pin "1") (pinfunction "1_1") (pintype "passive"))
      (node (ref "U1.1") (pin "6") (pinfunction "2-_6") (pintype "passive"))
    )
    (net (code "59") (name "Net-(U1.2A-1-)") (class "Default")
      (node (ref "C1.1") (pin "1") (pinfunction "1_1") (pintype "passive"))
      (node (ref "U1.2") (pin "1") (pinfunction "1O_1") (pintype "passive"))
      (node (ref "U1.2") (pin "2") (pinfunction "1-_2") (pintype "passive"))
    )
    (net (code "60") (name "Net-(U1.2B-2-)") (class "Default")
      (node (ref "C1.2") (pin "1") (pinfunction "1_1") (pintype "passive"))
      (node (ref "U1.2") (pin "6") (pinfunction "2-_6") (pintype "passive"))
      (node (ref "U1.2") (pin "7") (pinfunction "2O_7") (pintype "passive"))
    )
    (net (code "61") (name "Net-(U1.3-IN-)") (class "Default")
      (node (ref "R1.23") (pin "2") (pinfunction "2_2") (pintype "passive"))
      (node (ref "U1.3") (pin "3") (pinfunction "IN-_3") (pintype "passive"))
    )
    (net (code "62") (name "Net-(U1.4-IN-)") (class "Default")
      (node (ref "R1.24") (pin "2") (pinfunction "2_2") (pintype "passive"))
      (node (ref "U1.4") (pin "3") (pinfunction "IN-_3") (pintype "passive"))
    )
    (net (code "63") (name "Net-(U1.5-IN-)") (class "Default")
      (node (ref "R1.26") (pin "2") (pinfunction "2_2") (pintype "passive"))
      (node (ref "U1.5") (pin "3") (pinfunction "IN-_3") (pintype "passive"))
    )
    (net (code "64") (name "Net-(U1.6-IN-)") (class "Default")
      (node (ref "R1.28") (pin "2") (pinfunction "2_2") (pintype "passive"))
      (node (ref "U1.6") (pin "3") (pinfunction "IN-_3") (pintype "passive"))
    )
    (net (code "65") (name "Net-(U1.7-IN-)") (class "Default")
      (node (ref "R1.30") (pin "2") (pinfunction "2_2") (pintype "passive"))
      (node (ref "U1.7") (pin "3") (pinfunction "IN-_3") (pintype "passive"))
    )
    (net (code "66") (name "P_GND") (class "Default")
      (node (ref "C3.1") (pin "1") (pinfunction "1_1") (pintype "passive"))
      (node (ref "C3.2") (pin "1") (pinfunction "1_1") (pintype "passive"))
      (node (ref "C3.3") (pin "1") (pinfunction "1_1") (pintype "passive"))
      (node (ref "C4.1") (pin "1") (pinfunction "1_1") (pintype "passive"))
      (node (ref "C6.1") (pin "1") (pinfunction "1_1") (pintype "passive"))
      (node (ref "C6.2") (pin "1") (pinfunction "1_1") (pintype "passive"))
      (node (ref "C6.3") (pin "1") (pinfunction "1_1") (pintype "passive"))
      (node (ref "C6.4") (pin "1") (pinfunction "1_1") (pintype "passive"))
      (node (ref "C6.5") (pin "1") (pinfunction "1_1") (pintype "passive"))
      (node (ref "C6.6") (pin "1") (pinfunction "1_1") (pintype "passive"))
      (node (ref "D1.1") (pin "1") (pinfunction "Anode_1") (pintype "passive"))
      (node (ref "D1.2") (pin "1") (pinfunction "Anode_1") (pintype "passive"))
      (node (ref "J4.1") (pin "1") (pinfunction "1_1") (pintype "passive"))
      (node (ref "J4.10") (pin "1") (pinfunction "1_1") (pintype "passive"))
      (node (ref "J4.11") (pin "1") (pinfunction "1_1") (pintype "passive"))
      (node (ref "J4.12") (pin "1") (pinfunction "1_1") (pintype "passive"))
      (node (ref "J4.13") (pin "3") (pinfunction "3_3") (pintype "passive"))
      (node (ref "J4.14") (pin "1") (pinfunction "1_1") (pintype "passive"))
      (node (ref "J4.15") (pin "3") (pinfunction "3_3") (pintype "passive"))
      (node (ref "J4.16") (pin "3") (pinfunction "3_3") (pintype "passive"))
      (node (ref "J4.18") (pin "1") (pinfunction "1_1") (pintype "passive"))
      (node (ref "J4.2") (pin "1") (pinfunction "1_1") (pintype "passive"))
      (node (ref "J4.20") (pin "1") (pinfunction "1_1") (pintype "passive"))
      (node (ref "J4.21") (pin "1") (pinfunction "1_1") (pintype "passive"))
      (node (ref "J4.22") (pin "1") (pinfunction "1_1") (pintype "passive"))
      (node (ref "J4.26") (pin "3") (pinfunction "3_3") (pintype "passive"))
      (node (ref "J4.8") (pin "1") (pinfunction "1_1") (pintype "passive"))
      (node (ref "J4.9") (pin "1") (pinfunction "1_1") (pintype "passive"))
      (node (ref "R1.11") (pin "2") (pinfunction "2_2") (pintype "passive"))
      (node (ref "R1.13") (pin "1") (pinfunction "1_1") (pintype "passive"))
      (node (ref "R1.16") (pin "2") (pinfunction "2_2") (pintype "passive"))
      (node (ref "R1.18") (pin "1") (pinfunction "1_1") (pintype "passive"))
      (node (ref "R1.23") (pin "1") (pinfunction "1_1") (pintype "passive"))
      (node (ref "R1.24") (pin "1") (pinfunction "1_1") (pintype "passive"))
      (node (ref "R1.26") (pin "1") (pinfunction "1_1") (pintype "passive"))
      (node (ref "R1.28") (pin "1") (pinfunction "1_1") (pintype "passive"))
      (node (ref "R1.30") (pin "1") (pinfunction "1_1") (pintype "passive"))
      (node (ref "U1.1") (pin "3") (pinfunction "1+_3") (pintype "passive"))
      (node (ref "U1.1") (pin "4") (pinfunction "VCC-_4") (pintype "passive"))
      (node (ref "U1.1") (pin "5") (pinfunction "2+_5") (pintype "passive"))
      (node (ref "U1.2") (pin "4") (pinfunction "VCC-_4") (pintype "passive"))
      (node (ref "U1.3") (pin "1") (pinfunction "E_OUT_1") (pintype "passive"))
      (node (ref "U1.3") (pin "4") (pinfunction "VCC-_4") (pintype "passive"))
      (node (ref "U1.4") (pin "1") (pinfunction "E_OUT_1") (pintype "passive"))
      (node (ref "U1.4") (pin "4") (pinfunction "VCC-_4") (pintype "passive"))
      (node (ref "U1.5") (pin "1") (pinfunction "E_OUT_1") (pintype "passive"))
      (node (ref "U1.5") (pin "4") (pinfunction "VCC-_4") (pintype "passive"))
      (node (ref "U1.6") (pin "1") (pinfunction "E_OUT_1") (pintype "passive"))
      (node (ref "U1.6") (pin "4") (pinfunction "VCC-_4") (pintype "passive"))
      (node (ref "U1.7") (pin "1") (pinfunction "E_OUT_1") (pintype "passive"))
      (node (ref "U1.7") (pin "4") (pinfunction "VCC-_4") (pintype "passive"))
      (node (ref "U5.1") (pin "19") (pinfunction "GND_19") (pintype "passive"))
      (node (ref "U5.1") (pin "20") (pinfunction "GND_20") (pintype "passive"))
      (node (ref "U5.1") (pin "39") (pinfunction "GND_39") (pintype "passive"))
      (node (ref "U6.1") (pin "2") (pinfunction "GND_2") (pintype "passive"))
      (node (ref "U6.2") (pin "2") (pinfunction "GND_2") (pintype "passive"))
      (node (ref "U6.3") (pin "2") (pinfunction "GND_2") (pintype "passive"))
      (node (ref "U6.4") (pin "2") (pinfunction "IN-_2") (pintype "passive"))
      (node (ref "U6.4") (pin "3") (pinfunction "OUT-_3") (pintype "passive"))
    )
    (net (code "67") (name "unconnected-(J4.24-Pad1)") (class "Default")
      (node (ref "J4.24") (pin "1") (pinfunction "1_1") (pintype "passive"))
    )
    (net (code "68") (name "unconnected-(J4.24-Pad4)") (class "Default")
      (node (ref "J4.24") (pin "4") (pinfunction "4_4") (pintype "passive"))
    )
    (net (code "69") (name "unconnected-(J5.1-3V3-Pad1)") (class "Default")
      (node (ref "J5.1") (pin "1") (pinfunction "3V3_1") (pintype "passive"))
    )
    (net (code "70") (name "unconnected-(J5.1-GND-Pad4)") (class "Default")
      (node (ref "J5.1") (pin "4") (pinfunction "GND_4") (pintype "passive"))
    )
    (net (code "71") (name "unconnected-(R1.11-Pad1)") (class "Default")
      (node (ref "R1.11") (pin "1") (pinfunction "1_1") (pintype "passive"))
    )
    (net (code "72") (name "unconnected-(R1.14-Pad3)") (class "Default")
      (node (ref "R1.14") (pin "3") (pinfunction "3_3") (pintype "passive"))
    )
    (net (code "73") (name "unconnected-(R1.15-Pad3)") (class "Default")
      (node (ref "R1.15") (pin "3") (pinfunction "3_3") (pintype "passive"))
    )
    (net (code "74") (name "unconnected-(R1.16-Pad1)") (class "Default")
      (node (ref "R1.16") (pin "1") (pinfunction "1_1") (pintype "passive"))
    )
    (net (code "75") (name "unconnected-(R1.19-Pad3)") (class "Default")
      (node (ref "R1.19") (pin "3") (pinfunction "3_3") (pintype "passive"))
    )
    (net (code "76") (name "unconnected-(R1.20-Pad3)") (class "Default")
      (node (ref "R1.20") (pin "3") (pinfunction "3_3") (pintype "passive"))
    )
    (net (code "77") (name "unconnected-(U1.3-BAL-Pad5)") (class "Default")
      (node (ref "U1.3") (pin "5") (pinfunction "BAL_5") (pintype "passive"))
    )
    (net (code "78") (name "unconnected-(U1.3-STRB-Pad6)") (class "Default")
      (node (ref "U1.3") (pin "6") (pinfunction "STRB_6") (pintype "passive"))
    )
    (net (code "79") (name "unconnected-(U1.4-BAL-Pad5)") (class "Default")
      (node (ref "U1.4") (pin "5") (pinfunction "BAL_5") (pintype "passive"))
    )
    (net (code "80") (name "unconnected-(U1.4-STRB-Pad6)") (class "Default")
      (node (ref "U1.4") (pin "6") (pinfunction "STRB_6") (pintype "passive"))
    )
    (net (code "81") (name "unconnected-(U1.5-BAL-Pad5)") (class "Default")
      (node (ref "U1.5") (pin "5") (pinfunction "BAL_5") (pintype "passive"))
    )
    (net (code "82") (name "unconnected-(U1.5-STRB-Pad6)") (class "Default")
      (node (ref "U1.5") (pin "6") (pinfunction "STRB_6") (pintype "passive"))
    )
    (net (code "83") (name "unconnected-(U1.6-BAL-Pad5)") (class "Default")
      (node (ref "U1.6") (pin "5") (pinfunction "BAL_5") (pintype "passive"))
    )
    (net (code "84") (name "unconnected-(U1.6-STRB-Pad6)") (class "Default")
      (node (ref "U1.6") (pin "6") (pinfunction "STRB_6") (pintype "passive"))
    )
    (net (code "85") (name "unconnected-(U1.7-BAL-Pad5)") (class "Default")
      (node (ref "U1.7") (pin "5") (pinfunction "BAL_5") (pintype "passive"))
    )
    (net (code "86") (name "unconnected-(U1.7-STRB-Pad6)") (class "Default")
      (node (ref "U1.7") (pin "6") (pinfunction "STRB_6") (pintype "passive"))
    )
    (net (code "87") (name "unconnected-(U5.1-5V-Pad38)") (class "Default")
      (node (ref "U5.1") (pin "38") (pinfunction "5V_38") (pintype "passive"))
    )
    (net (code "88") (name "unconnected-(U5.1-NRST-Pad17)") (class "Default")
      (node (ref "U5.1") (pin "17") (pinfunction "NRST_17") (pintype "passive"))
    )
    (net (code "89") (name "unconnected-(U5.1-PC13-Pad2)") (class "Default")
      (node (ref "U5.1") (pin "2") (pinfunction "PC13_2") (pintype "passive"))
    )
    (net (code "90") (name "unconnected-(U5.1-PC14-Pad3)") (class "Default")
      (node (ref "U5.1") (pin "3") (pinfunction "PC14_3") (pintype "passive"))
    )
    (net (code "91") (name "unconnected-(U5.1-PC15-Pad4)") (class "Default")
      (node (ref "U5.1") (pin "4") (pinfunction "PC15_4") (pintype "passive"))
    )
  )
)
